# OSO-SAFE-A1-03.net
KiCad netlist of a schematic drawn in EAGLE
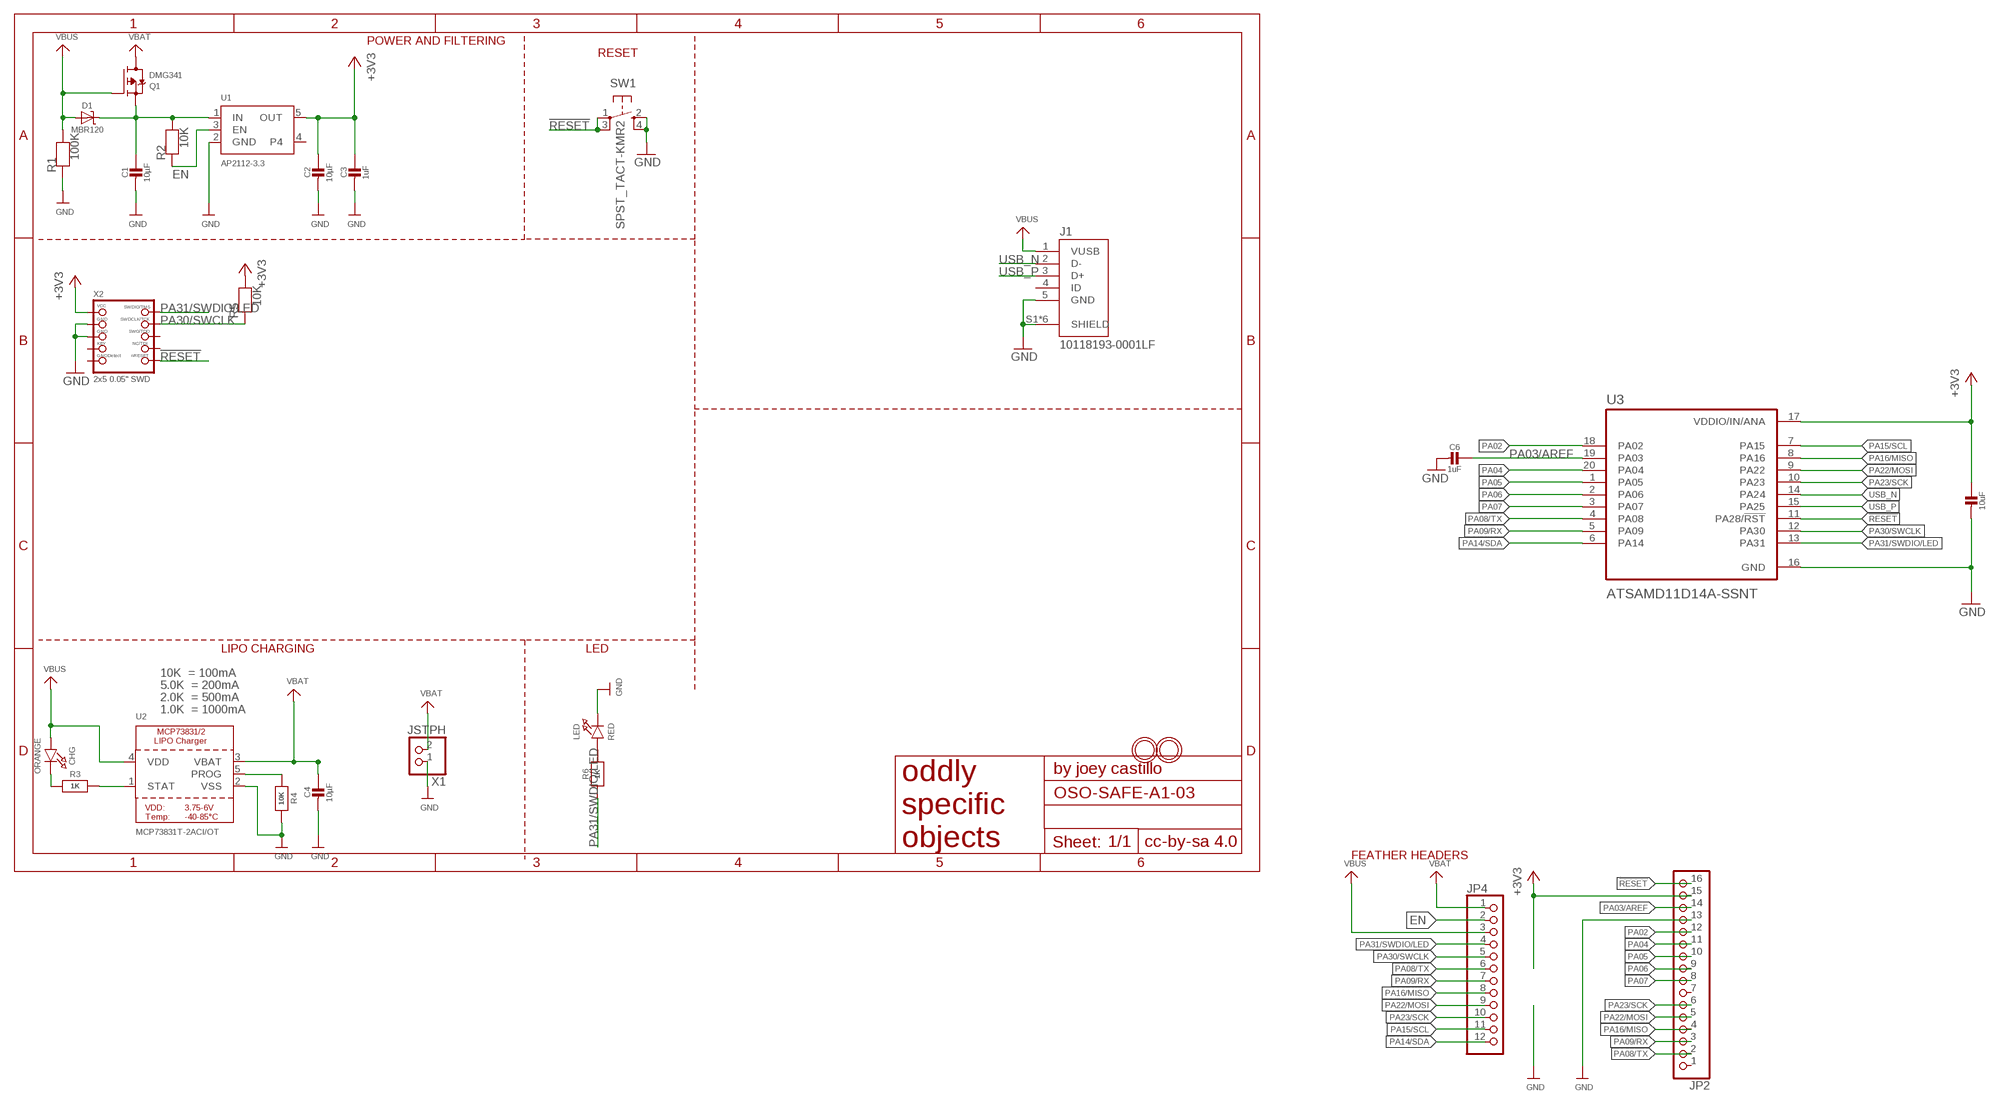
[diagram p0: schematic, sheet 1]

(export (version "E")
  (design (tool "Eeschema 10.0.6"))
  (components
    (comp (ref "C1")
      (value "10µF")
      (footprint "eagle-import:0805-NO")
      (libsource (lib "eagle-import") (part "CAP_CERAMIC0805-NOOUTLINE"))
    )
    (comp (ref "C2")
      (value "10µF")
      (footprint "eagle-import:0805-NO")
      (libsource (lib "eagle-import") (part "CAP_CERAMIC0805-NOOUTLINE"))
    )
    (comp (ref "C3")
      (value "1uF")
      (footprint "eagle-import:0805-NO")
      (libsource (lib "eagle-import") (part "CAP_CERAMIC0805-NOOUTLINE"))
    )
    (comp (ref "C4")
      (value "10µF")
      (footprint "eagle-import:0805-NO")
      (libsource (lib "eagle-import") (part "CAP_CERAMIC0805-NOOUTLINE"))
    )
    (comp (ref "C5")
      (value "10uF")
      (footprint "eagle-import:0805-NO")
      (libsource (lib "eagle-import") (part "CAP_CERAMIC0805-NOOUTLINE"))
    )
    (comp (ref "C6")
      (value "1uF")
      (footprint "eagle-import:0805-NO")
      (libsource (lib "eagle-import") (part "CAP_CERAMIC0805-NOOUTLINE"))
    )
    (comp (ref "CHG")
      (value "ORANGE")
      (footprint "eagle-import:CHIPLED_0805_NOOUTLINE")
      (libsource (lib "eagle-import") (part "LED0805_NOOUTLINE"))
    )
    (comp (ref "D1")
      (value "MBR120")
      (footprint "eagle-import:SOD-123")
      (libsource (lib "eagle-import") (part "DIODE-SCHOTTKYSOD-123"))
    )
    (comp (ref "J1")
      (value "10118193-0001LF")
      (footprint "eagle-import:FCI_10118193-0001LF")
      (fields (field (name "DIGI-KEY_PART_NUMBER") "609-4616-1-ND") (field (name "MF") "Amphenol ICC"))
      (libsource (lib "eagle-import") (part "10118193-0001LF"))
    )
    (comp (ref "JP2")
      (value "HEADER-1X16_MIN")
      (footprint "eagle-import:1X16_ROUND_MIN")
      (libsource (lib "eagle-import") (part "HEADER-1X16_MIN"))
    )
    (comp (ref "JP4")
      (value "HEADER-1X12_MIN")
      (footprint "eagle-import:1X12_ROUND_MIN")
      (libsource (lib "eagle-import") (part "HEADER-1X12_MIN"))
    )
    (comp (ref "LED")
      (value "RED")
      (footprint "eagle-import:CHIPLED_0805_NOOUTLINE")
      (libsource (lib "eagle-import") (part "LED0805_NOOUTLINE"))
    )
    (comp (ref "Q1")
      (value "DMG341")
      (footprint "eagle-import:SOT23-R")
      (libsource (lib "eagle-import") (part "MOSFET-P"))
    )
    (comp (ref "R1")
      (value "100K")
      (footprint "eagle-import:0805-NO")
      (libsource (lib "eagle-import") (part "RESISTOR0805_NOOUTLINE"))
    )
    (comp (ref "R2")
      (value "10K")
      (footprint "eagle-import:0805-NO")
      (libsource (lib "eagle-import") (part "RESISTOR0805_NOOUTLINE"))
    )
    (comp (ref "R3")
      (value "1K")
      (footprint "eagle-import:0805-NO")
      (libsource (lib "eagle-import") (part "RESISTOR0805_NOOUTLINE"))
    )
    (comp (ref "R4")
      (value "10K")
      (footprint "eagle-import:0805-NO")
      (libsource (lib "eagle-import") (part "RESISTOR0805_NOOUTLINE"))
    )
    (comp (ref "R5")
      (value "10K")
      (footprint "eagle-import:0805-NO")
      (libsource (lib "eagle-import") (part "RESISTOR0805_NOOUTLINE"))
    )
    (comp (ref "R6")
      (value "1K")
      (footprint "eagle-import:0805-NO")
      (libsource (lib "eagle-import") (part "RESISTOR0805_NOOUTLINE"))
    )
    (comp (ref "SW1")
      (value "SPST_TACT-KMR2")
      (footprint "eagle-import:KMR2")
      (libsource (lib "eagle-import") (part "SPST_TACT-KMR2"))
    )
    (comp (ref "U$31")
      (value "MOUNTINGHOLE2.5")
      (footprint "eagle-import:MOUNTINGHOLE_2.5_PLATED")
      (libsource (lib "eagle-import") (part "MOUNTINGHOLE2.5"))
    )
    (comp (ref "U$32")
      (value "MOUNTINGHOLE2.5")
      (footprint "eagle-import:MOUNTINGHOLE_2.5_PLATED")
      (libsource (lib "eagle-import") (part "MOUNTINGHOLE2.5"))
    )
    (comp (ref "U1")
      (value "AP2112-3.3")
      (footprint "eagle-import:SOT23-5")
      (libsource (lib "eagle-import") (part "VREG_SOT23-5"))
    )
    (comp (ref "U2")
      (value "MCP73831T-2ACI/OT")
      (footprint "eagle-import:SOT23-5")
      (libsource (lib "eagle-import") (part "MCP73831/2"))
    )
    (comp (ref "U3")
      (value "ATSAMD11D14A-SSNT")
      (footprint "eagle-import:SOIC127P1030X265-20N")
      (fields (field (name "MF") "Microchip"))
      (libsource (lib "eagle-import") (part "ATSAMD11D14A-SSNT"))
    )
    (comp (ref "X1")
      (value "JSTPH")
      (footprint "eagle-import:JSTPH2")
      (libsource (lib "eagle-import") (part "CON_JST_PH_2PIN"))
    )
    (comp (ref "X2")
      (value "2x5 0.05\" SWD")
      (footprint "eagle-import:2X05_1.27MM_BOX_POSTS")
      (libsource (lib "eagle-import") (part "JTAG-CORTEXBOXPOSTS"))
    )
  )
  (nets
    (net (code "1") (name "+3V3") (class "Default")
      (node (ref "C2") (pin "1") (pinfunction "1_1") (pintype "passive"))
      (node (ref "C3") (pin "1") (pinfunction "1_1") (pintype "passive"))
      (node (ref "C5") (pin "1") (pinfunction "1_1") (pintype "passive"))
      (node (ref "JP2") (pin "15") (pinfunction "15_15") (pintype "passive"))
      (node (ref "R5") (pin "2") (pinfunction "2_2") (pintype "passive"))
      (node (ref "U1") (pin "5") (pinfunction "OUT_5") (pintype "power_in"))
      (node (ref "U3") (pin "17") (pinfunction "VDDIO/IN/ANA_17") (pintype "power_in"))
      (node (ref "X2") (pin "1") (pinfunction "VCC_1") (pintype "power_in"))
    )
    (net (code "2") (name "/~{RESET}") (class "Default")
      (node (ref "JP2") (pin "16") (pinfunction "16_16") (pintype "passive"))
      (node (ref "SW1") (pin "1") (pinfunction "P_1") (pintype "passive"))
      (node (ref "SW1") (pin "3") (pinfunction "P1_3") (pintype "passive"))
      (node (ref "U3") (pin "11") (pinfunction "PA28/~{RST}_11") (pintype "bidirectional"))
      (node (ref "X2") (pin "10") (pinfunction "NRESET_10") (pintype "bidirectional"))
    )
    (net (code "3") (name "EN") (class "Default")
      (node (ref "JP4") (pin "2") (pinfunction "2_2") (pintype "passive"))
      (node (ref "R2") (pin "1") (pinfunction "1_1") (pintype "passive"))
      (node (ref "U1") (pin "3") (pinfunction "EN_3") (pintype "input"))
    )
    (net (code "4") (name "GND") (class "Default")
      (node (ref "C1") (pin "2") (pinfunction "2_2") (pintype "passive"))
      (node (ref "C2") (pin "2") (pinfunction "2_2") (pintype "passive"))
      (node (ref "C3") (pin "2") (pinfunction "2_2") (pintype "passive"))
      (node (ref "C4") (pin "2") (pinfunction "2_2") (pintype "passive"))
      (node (ref "C5") (pin "2") (pinfunction "2_2") (pintype "passive"))
      (node (ref "C6") (pin "2") (pinfunction "2_2") (pintype "passive"))
      (node (ref "J1") (pin "5") (pinfunction "GND_5") (pintype "passive"))
      (node (ref "J1") (pin "S1") (pinfunction "SHIELD_S1") (pintype "passive"))
      (node (ref "J1") (pin "S2") (pinfunction "SHIELD_S2") (pintype "passive"))
      (node (ref "J1") (pin "S3") (pinfunction "SHIELD_S3") (pintype "passive"))
      (node (ref "J1") (pin "S4") (pinfunction "SHIELD_S4") (pintype "passive"))
      (node (ref "J1") (pin "S5") (pinfunction "SHIELD_S5") (pintype "passive"))
      (node (ref "J1") (pin "S6") (pinfunction "SHIELD_S6") (pintype "passive"))
      (node (ref "JP2") (pin "13") (pinfunction "13_13") (pintype "passive"))
      (node (ref "LED") (pin "C") (pinfunction "C_C") (pintype "passive"))
      (node (ref "R1") (pin "1") (pinfunction "1_1") (pintype "passive"))
      (node (ref "R4") (pin "2") (pinfunction "2_2") (pintype "passive"))
      (node (ref "SW1") (pin "2") (pinfunction "S_2") (pintype "passive"))
      (node (ref "SW1") (pin "4") (pinfunction "S1_4") (pintype "passive"))
      (node (ref "U1") (pin "2") (pinfunction "GND_2") (pintype "power_in"))
      (node (ref "U2") (pin "2") (pinfunction "VSS_2") (pintype "power_in"))
      (node (ref "U3") (pin "16") (pinfunction "GND_16") (pintype "power_in"))
      (node (ref "X1") (pin "1") (pinfunction "1_1") (pintype "passive"))
      (node (ref "X2") (pin "3") (pinfunction "GND_3") (pintype "power_in"))
      (node (ref "X2") (pin "5") (pinfunction "GND_5") (pintype "power_in"))
    )
    (net (code "5") (name "Net-(CHG-PadC)") (class "Default")
      (node (ref "CHG") (pin "C") (pinfunction "C_C") (pintype "passive"))
      (node (ref "R3") (pin "1") (pinfunction "1_1") (pintype "passive"))
    )
    (net (code "6") (name "Net-(LED-PadA)") (class "Default")
      (node (ref "LED") (pin "A") (pinfunction "A_A") (pintype "passive"))
      (node (ref "R6") (pin "2") (pinfunction "2_2") (pintype "passive"))
    )
    (net (code "7") (name "Net-(Q1-S)") (class "Default")
      (node (ref "C1") (pin "1") (pinfunction "1_1") (pintype "passive"))
      (node (ref "D1") (pin "C") (pinfunction "C_C") (pintype "passive"))
      (node (ref "Q1") (pin "2") (pinfunction "S_2") (pintype "passive"))
      (node (ref "R2") (pin "2") (pinfunction "2_2") (pintype "passive"))
      (node (ref "U1") (pin "1") (pinfunction "IN_1") (pintype "power_in"))
    )
    (net (code "8") (name "Net-(U2-PROG)") (class "Default")
      (node (ref "R4") (pin "1") (pinfunction "1_1") (pintype "passive"))
      (node (ref "U2") (pin "5") (pinfunction "PROG_5") (pintype "input"))
    )
    (net (code "9") (name "Net-(U2-STAT)") (class "Default")
      (node (ref "R3") (pin "2") (pinfunction "2_2") (pintype "passive"))
      (node (ref "U2") (pin "1") (pinfunction "STAT_1") (pintype "output"))
    )
    (net (code "10") (name "PA02") (class "Default")
      (node (ref "JP2") (pin "12") (pinfunction "12_12") (pintype "passive"))
      (node (ref "U3") (pin "18") (pinfunction "PA02_18") (pintype "bidirectional"))
    )
    (net (code "11") (name "PA03{slash}AREF") (class "Default")
      (node (ref "C6") (pin "1") (pinfunction "1_1") (pintype "passive"))
      (node (ref "JP2") (pin "14") (pinfunction "14_14") (pintype "passive"))
      (node (ref "U3") (pin "19") (pinfunction "PA03_19") (pintype "bidirectional"))
    )
    (net (code "12") (name "PA04") (class "Default")
      (node (ref "JP2") (pin "11") (pinfunction "11_11") (pintype "passive"))
      (node (ref "U3") (pin "20") (pinfunction "PA04_20") (pintype "bidirectional"))
    )
    (net (code "13") (name "PA05") (class "Default")
      (node (ref "JP2") (pin "10") (pinfunction "10_10") (pintype "passive"))
      (node (ref "U3") (pin "1") (pinfunction "PA05_1") (pintype "bidirectional"))
    )
    (net (code "14") (name "PA06") (class "Default")
      (node (ref "JP2") (pin "9") (pinfunction "9_9") (pintype "passive"))
      (node (ref "U3") (pin "2") (pinfunction "PA06_2") (pintype "bidirectional"))
    )
    (net (code "15") (name "PA07") (class "Default")
      (node (ref "JP2") (pin "8") (pinfunction "8_8") (pintype "passive"))
      (node (ref "U3") (pin "3") (pinfunction "PA07_3") (pintype "bidirectional"))
    )
    (net (code "16") (name "PA08{slash}TX") (class "Default")
      (node (ref "JP2") (pin "2") (pinfunction "2_2") (pintype "passive"))
      (node (ref "JP4") (pin "6") (pinfunction "6_6") (pintype "passive"))
      (node (ref "U3") (pin "4") (pinfunction "PA08_4") (pintype "bidirectional"))
    )
    (net (code "17") (name "PA09{slash}RX") (class "Default")
      (node (ref "JP2") (pin "3") (pinfunction "3_3") (pintype "passive"))
      (node (ref "JP4") (pin "7") (pinfunction "7_7") (pintype "passive"))
      (node (ref "U3") (pin "5") (pinfunction "PA09_5") (pintype "bidirectional"))
    )
    (net (code "18") (name "PA14{slash}SDA") (class "Default")
      (node (ref "JP4") (pin "12") (pinfunction "12_12") (pintype "passive"))
      (node (ref "U3") (pin "6") (pinfunction "PA14_6") (pintype "bidirectional"))
    )
    (net (code "19") (name "PA15{slash}SCL") (class "Default")
      (node (ref "JP4") (pin "11") (pinfunction "11_11") (pintype "passive"))
      (node (ref "U3") (pin "7") (pinfunction "PA15_7") (pintype "bidirectional"))
    )
    (net (code "20") (name "PA16{slash}MISO") (class "Default")
      (node (ref "JP2") (pin "4") (pinfunction "4_4") (pintype "passive"))
      (node (ref "JP4") (pin "8") (pinfunction "8_8") (pintype "passive"))
      (node (ref "U3") (pin "8") (pinfunction "PA16_8") (pintype "bidirectional"))
    )
    (net (code "21") (name "PA22{slash}MOSI") (class "Default")
      (node (ref "JP2") (pin "5") (pinfunction "5_5") (pintype "passive"))
      (node (ref "JP4") (pin "9") (pinfunction "9_9") (pintype "passive"))
      (node (ref "U3") (pin "9") (pinfunction "PA22_9") (pintype "bidirectional"))
    )
    (net (code "22") (name "PA23{slash}SCK") (class "Default")
      (node (ref "JP2") (pin "6") (pinfunction "6_6") (pintype "passive"))
      (node (ref "JP4") (pin "10") (pinfunction "10_10") (pintype "passive"))
      (node (ref "U3") (pin "10") (pinfunction "PA23_10") (pintype "bidirectional"))
    )
    (net (code "23") (name "PA30{slash}SWCLK") (class "Default")
      (node (ref "JP4") (pin "5") (pinfunction "5_5") (pintype "passive"))
      (node (ref "R5") (pin "1") (pinfunction "1_1") (pintype "passive"))
      (node (ref "U3") (pin "12") (pinfunction "PA30_12") (pintype "bidirectional"))
      (node (ref "X2") (pin "4") (pinfunction "SWDCLK_4") (pintype "bidirectional"))
    )
    (net (code "24") (name "PA31{slash}SWDIO{slash}LED") (class "Default")
      (node (ref "JP4") (pin "4") (pinfunction "4_4") (pintype "passive"))
      (node (ref "R6") (pin "1") (pinfunction "1_1") (pintype "passive"))
      (node (ref "U3") (pin "13") (pinfunction "PA31_13") (pintype "bidirectional"))
      (node (ref "X2") (pin "2") (pinfunction "SWDIO_2") (pintype "bidirectional"))
    )
    (net (code "25") (name "USB_N") (class "Default")
      (node (ref "J1") (pin "2") (pinfunction "D-_2") (pintype "passive"))
      (node (ref "U3") (pin "14") (pinfunction "PA24_14") (pintype "bidirectional"))
    )
    (net (code "26") (name "USB_P") (class "Default")
      (node (ref "J1") (pin "3") (pinfunction "D+_3") (pintype "passive"))
      (node (ref "U3") (pin "15") (pinfunction "PA25_15") (pintype "bidirectional"))
    )
    (net (code "27") (name "VBAT") (class "Default")
      (node (ref "C4") (pin "1") (pinfunction "1_1") (pintype "passive"))
      (node (ref "JP4") (pin "1") (pinfunction "1_1") (pintype "passive"))
      (node (ref "Q1") (pin "3") (pinfunction "D_3") (pintype "passive"))
      (node (ref "U2") (pin "3") (pinfunction "VBAT_3") (pintype "power_in"))
      (node (ref "X1") (pin "2") (pinfunction "2_2") (pintype "passive"))
    )
    (net (code "28") (name "VBUS") (class "Default")
      (node (ref "CHG") (pin "A") (pinfunction "A_A") (pintype "passive"))
      (node (ref "D1") (pin "A") (pinfunction "A_A") (pintype "passive"))
      (node (ref "J1") (pin "1") (pinfunction "VUSB_1") (pintype "passive"))
      (node (ref "JP4") (pin "3") (pinfunction "3_3") (pintype "passive"))
      (node (ref "Q1") (pin "1") (pinfunction "G_1") (pintype "passive"))
      (node (ref "R1") (pin "2") (pinfunction "2_2") (pintype "passive"))
      (node (ref "U2") (pin "4") (pinfunction "VDD_4") (pintype "power_in"))
    )
    (net (code "29") (name "unconnected-(J1-ID-Pad4)") (class "Default")
      (node (ref "J1") (pin "4") (pinfunction "ID_4") (pintype "passive"))
    )
    (net (code "30") (name "unconnected-(JP2-Pad1)") (class "Default")
      (node (ref "JP2") (pin "1") (pinfunction "1_1") (pintype "passive"))
    )
    (net (code "31") (name "unconnected-(JP2-Pad7)") (class "Default")
      (node (ref "JP2") (pin "7") (pinfunction "7_7") (pintype "passive"))
    )
    (net (code "32") (name "unconnected-(U1-P4-Pad4)") (class "Default")
      (node (ref "U1") (pin "4") (pinfunction "P4_4") (pintype "bidirectional"))
    )
    (net (code "33") (name "unconnected-(X2-GNDDETECT-Pad9)") (class "Default")
      (node (ref "X2") (pin "9") (pinfunction "GNDDETECT_9") (pintype "bidirectional"))
    )
    (net (code "34") (name "unconnected-(X2-KEY-Pad7)") (class "Default")
      (node (ref "X2") (pin "7") (pinfunction "KEY_7") (pintype "bidirectional"))
    )
    (net (code "35") (name "unconnected-(X2-SWO-Pad6)") (class "Default")
      (node (ref "X2") (pin "6") (pinfunction "SWO_6") (pintype "bidirectional"))
    )
    (net (code "36") (name "unconnected-(X2-TDI-Pad8)") (class "Default")
      (node (ref "X2") (pin "8") (pinfunction "TDI_8") (pintype "bidirectional"))
    )
  )
)
